# CH32V305FBP6-R0.net
KiCad netlist of a schematic drawn in Altium Designer
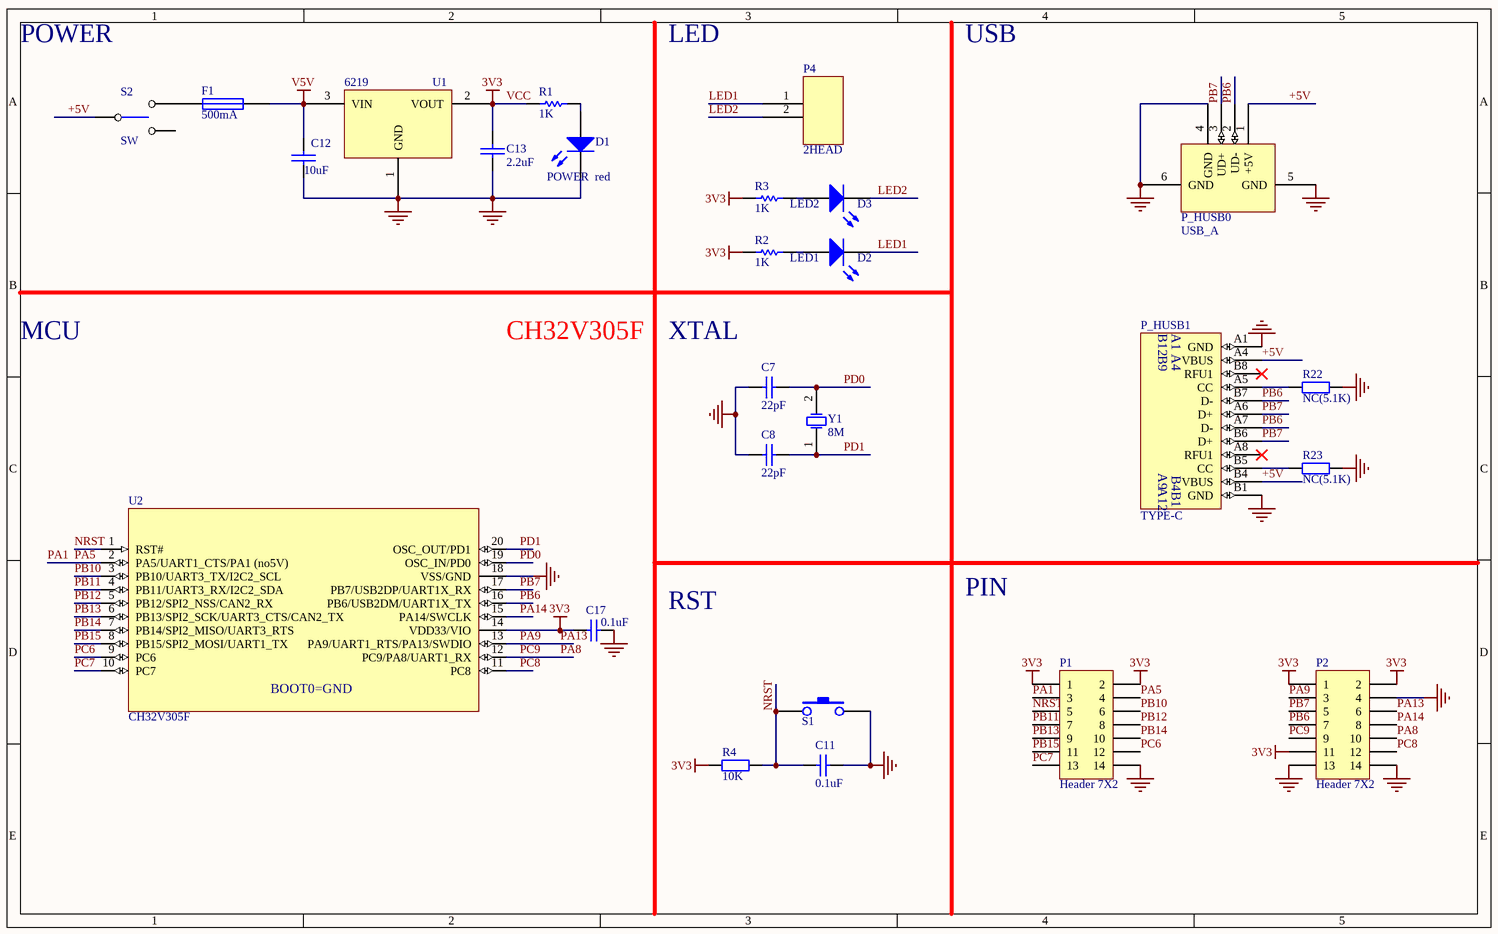
[diagram p0: CH32V305FBP6-R0.SchDoc]

(export (version "E")
  (design (tool "Eeschema 10.0.6"))
  (components
    (comp (ref "C7")
      (value "22pF")
      (footprint "0603_C")
      (description "Capacitor")
      (fields (field (name "PUBLISHER") "Altium Limited"))
      (libsource (lib "*") (part "Cap"))
    )
    (comp (ref "C8")
      (value "22pF")
      (footprint "0603_C")
      (description "Capacitor")
      (fields (field (name "PUBLISHER") "Altium Limited"))
      (libsource (lib "*") (part "Cap"))
    )
    (comp (ref "C11")
      (value "0.1uF")
      (footprint "0603_C")
      (description "Capacitor")
      (fields (field (name "PUBLISHER") "Altium Limited"))
      (libsource (lib "*") (part "Cap"))
    )
    (comp (ref "C12")
      (value "10uF")
      (footprint "3216_C")
      (description "Capacitor")
      (libsource (lib "*") (part "CAP"))
    )
    (comp (ref "C13")
      (value "2.2uF")
      (footprint "0603_C")
      (description "Capacitor")
      (libsource (lib "*") (part "CAP"))
    )
    (comp (ref "C17")
      (value "0.1uF")
      (footprint "0603_C")
      (description "Capacitor")
      (fields (field (name "PUBLISHER") "Altium Limited"))
      (libsource (lib "*") (part "Cap"))
    )
    (comp (ref "D1")
      (value "POWER  red")
      (footprint "0603+")
      (description "Typical INFRARED GaAs LED")
      (fields (field (name "PUBLISHER") "Altium Limited"))
      (libsource (lib "*") (part "LED0"))
    )
    (comp (ref "D2")
      (value "LED1")
      (footprint "0603+")
      (description "Typical INFRARED GaAs LED")
      (fields (field (name "PUBLISHER") "Altium Limited"))
      (libsource (lib "*") (part "LED0"))
    )
    (comp (ref "D3")
      (value "LED2")
      (footprint "0603+")
      (description "Typical INFRARED GaAs LED")
      (fields (field (name "PUBLISHER") "Altium Limited"))
      (libsource (lib "*") (part "LED0"))
    )
    (comp (ref "F1")
      (value "500mA")
      (footprint "0603")
      (description "Fuse")
      (libsource (lib "*") (part "FUSE1"))
    )
    (comp (ref "P1")
      (value "Header 7X2")
      (footprint "IDC14-2.54mm")
      (description "Header, 7-Pin, Dual row")
      (fields (field (name "PUBLISHER") "Altium Limited"))
      (libsource (lib "Miscellaneous Connectors") (part "Header 7X2"))
    )
    (comp (ref "P2")
      (value "Header 7X2")
      (footprint "IDC14-2.54mm")
      (description "Header, 7-Pin, Dual row")
      (fields (field (name "PUBLISHER") "Altium Limited"))
      (libsource (lib "Miscellaneous Connectors") (part "Header 7X2"))
    )
    (comp (ref "P4") (value "2HEAD") (footprint "SIP2-2.54mm") (libsource (lib "*") (part "2HEAD")))
    (comp (ref "P_HUSB0")
      (value "USB_A")
      (footprint "USBAF")
      (description "USB Port")
      (libsource (lib "*") (part "USB"))
    )
    (comp (ref "P_HUSB1")
      (value "TYPE-C")
      (footprint "TYPE-C-Receptacle-2.0")
      (libsource (lib "*") (part "TYPE-C1"))
    )
    (comp (ref "R1")
      (value "1K")
      (footprint "0603")
      (description "Semiconductor Resistor")
      (fields (field (name "PUBLISHER") "Altium Limited"))
      (libsource (lib "*") (part "Res Semi"))
    )
    (comp (ref "R2")
      (value "1K")
      (footprint "0603")
      (description "Semiconductor Resistor")
      (fields (field (name "PUBLISHER") "Altium Limited"))
      (libsource (lib "*") (part "Res Semi"))
    )
    (comp (ref "R3")
      (value "1K")
      (footprint "0603")
      (description "Semiconductor Resistor")
      (fields (field (name "PUBLISHER") "Altium Limited"))
      (libsource (lib "*") (part "Res Semi"))
    )
    (comp (ref "R4")
      (value "10K")
      (footprint "0603")
      (description "Resistor")
      (fields (field (name "PUBLISHER") "Altium Limited"))
      (libsource (lib "*") (part "Res2"))
    )
    (comp (ref "R22")
      (value "NC(5.1K)")
      (footprint "0603")
      (description "Resistor")
      (libsource (lib "Miscellaneous Devices") (part "Res2"))
    )
    (comp (ref "R23")
      (value "NC(5.1K)")
      (footprint "0603")
      (description "Resistor")
      (libsource (lib "Miscellaneous Devices") (part "Res2"))
    )
    (comp (ref "S1") (value "KEY") (footprint "SMD_6.1x3.65x2.5mm-KEY") (libsource (lib "*") (part "KEY")))
    (comp (ref "S2") (value "SW") (footprint "KEY2") (libsource (lib "*") (part "SW")))
    (comp (ref "U1") (value "6219") (footprint "SOT-23") (libsource (lib "*") (part "LM1117_3.3V")))
    (comp (ref "U2")
      (value "CH32V305F")
      (footprint "TSSOP20")
      (description "RISC-V FPU HD-MCU, 144MHz, USB_480M, CAN, UART*2, SPI")
      (libsource (lib "CHXXX") (part "CH32V305F"))
    )
    (comp (ref "Y1")
      (value "8M")
      (footprint "XT_AT49")
      (description "Crystal Oscillator")
      (fields (field (name "PUBLISHER") "Altium Limited"))
      (libsource (lib "*") (part "XTAL"))
    )
  )
  (nets
    (net (code "1") (name "/+5V") (class "Default")
      (node (ref "P_HUSB0") (pin "1") (pinfunction "+5V_1") (pintype "power_in"))
      (node (ref "P_HUSB1") (pin "A4") (pinfunction "VBUS_A4") (pintype "bidirectional"))
      (node (ref "P_HUSB1") (pin "B4") (pinfunction "VBUS_B4") (pintype "bidirectional"))
      (node (ref "S2") (pin "1") (pinfunction "1_1") (pintype "passive"))
    )
    (net (code "3") (name "/LED1") (class "Default")
      (node (ref "D2") (pin "2") (pinfunction "K_2") (pintype "passive"))
      (node (ref "P4") (pin "1") (pintype "passive"))
    )
    (net (code "4") (name "/LED2") (class "Default")
      (node (ref "D3") (pin "2") (pinfunction "K_2") (pintype "passive"))
      (node (ref "P4") (pin "2") (pintype "passive"))
    )
    (net (code "5") (name "/NRST") (class "Default")
      (node (ref "C11") (pin "2") (pinfunction "2_2") (pintype "passive"))
      (node (ref "P1") (pin "5") (pinfunction "5_5") (pintype "passive"))
      (node (ref "R4") (pin "1") (pinfunction "1_1") (pintype "passive"))
      (node (ref "S1") (pin "1") (pinfunction "1_1") (pintype "passive"))
      (node (ref "U2") (pin "1") (pinfunction "RST#_1") (pintype "input"))
    )
    (net (code "6") (name "/PA1") (class "Default")
      (node (ref "P1") (pin "3") (pinfunction "3_3") (pintype "passive"))
      (node (ref "P1") (pin "4") (pinfunction "4_4") (pintype "passive"))
      (node (ref "U2") (pin "2") (pinfunction "PA5/UART1_CTS/PA1_(no5V)_2") (pintype "bidirectional"))
    )
    (net (code "7") (name "/PA8") (class "Default")
      (node (ref "P2") (pin "10") (pinfunction "10_10") (pintype "passive"))
      (node (ref "P2") (pin "9") (pinfunction "9_9") (pintype "passive"))
      (node (ref "U2") (pin "12") (pinfunction "PC9/PA8/UART1_RX_12") (pintype "bidirectional"))
    )
    (net (code "8") (name "/PA13") (class "Default")
      (node (ref "P2") (pin "3") (pinfunction "3_3") (pintype "passive"))
      (node (ref "P2") (pin "6") (pinfunction "6_6") (pintype "passive"))
      (node (ref "U2") (pin "13") (pinfunction "PA9/UART1_RTS/PA13/SWDIO_13") (pintype "bidirectional"))
    )
    (net (code "9") (name "/PA14") (class "Default")
      (node (ref "P2") (pin "8") (pinfunction "8_8") (pintype "passive"))
      (node (ref "U2") (pin "15") (pinfunction "PA14/SWCLK_15") (pintype "bidirectional"))
    )
    (net (code "10") (name "/PB6") (class "Default")
      (node (ref "P2") (pin "7") (pinfunction "7_7") (pintype "passive"))
      (node (ref "P_HUSB0") (pin "2") (pinfunction "UD-_2") (pintype "bidirectional"))
      (node (ref "P_HUSB1") (pin "A7") (pinfunction "D-_A7") (pintype "bidirectional"))
      (node (ref "P_HUSB1") (pin "B7") (pinfunction "D-_B7") (pintype "bidirectional"))
      (node (ref "U2") (pin "16") (pinfunction "PB6/USB2DM/UART1X_TX_16") (pintype "bidirectional"))
    )
    (net (code "11") (name "/PB7") (class "Default")
      (node (ref "P2") (pin "5") (pinfunction "5_5") (pintype "passive"))
      (node (ref "P_HUSB0") (pin "3") (pinfunction "UD+_3") (pintype "bidirectional"))
      (node (ref "P_HUSB1") (pin "A6") (pinfunction "D+_A6") (pintype "bidirectional"))
      (node (ref "P_HUSB1") (pin "B6") (pinfunction "D+_B6") (pintype "bidirectional"))
      (node (ref "U2") (pin "17") (pinfunction "PB7/USB2DP/UART1X_RX_17") (pintype "bidirectional"))
    )
    (net (code "12") (name "/PB10") (class "Default")
      (node (ref "P1") (pin "6") (pinfunction "6_6") (pintype "passive"))
      (node (ref "U2") (pin "3") (pinfunction "PB10/UART3_TX/I2C2_SCL_3") (pintype "bidirectional"))
    )
    (net (code "13") (name "/PB11") (class "Default")
      (node (ref "P1") (pin "7") (pinfunction "7_7") (pintype "passive"))
      (node (ref "U2") (pin "4") (pinfunction "PB11/UART3_RX/I2C2_SDA_4") (pintype "bidirectional"))
    )
    (net (code "14") (name "/PB12") (class "Default")
      (node (ref "P1") (pin "8") (pinfunction "8_8") (pintype "passive"))
      (node (ref "U2") (pin "5") (pinfunction "PB12/SPI2_NSS/CAN2_RX_5") (pintype "bidirectional"))
    )
    (net (code "15") (name "/PB13") (class "Default")
      (node (ref "P1") (pin "9") (pinfunction "9_9") (pintype "passive"))
      (node (ref "U2") (pin "6") (pinfunction "PB13/SPI2_SCK/UART3_CTS/CAN2_TX_6") (pintype "bidirectional"))
    )
    (net (code "16") (name "/PB14") (class "Default")
      (node (ref "P1") (pin "10") (pinfunction "10_10") (pintype "passive"))
      (node (ref "U2") (pin "7") (pinfunction "PB14/SPI2_MISO/UART3_RTS_7") (pintype "bidirectional"))
    )
    (net (code "17") (name "/PB15") (class "Default")
      (node (ref "P1") (pin "11") (pinfunction "11_11") (pintype "passive"))
      (node (ref "U2") (pin "8") (pinfunction "PB15/SPI2_MOSI/UART1_TX_8") (pintype "bidirectional"))
    )
    (net (code "18") (name "/PC6") (class "Default")
      (node (ref "P1") (pin "12") (pinfunction "12_12") (pintype "passive"))
      (node (ref "U2") (pin "9") (pinfunction "PC6_9") (pintype "bidirectional"))
    )
    (net (code "19") (name "/PC7") (class "Default")
      (node (ref "P1") (pin "13") (pinfunction "13_13") (pintype "passive"))
      (node (ref "U2") (pin "10") (pinfunction "PC7_10") (pintype "bidirectional"))
    )
    (net (code "20") (name "/PC8") (class "Default")
      (node (ref "P2") (pin "12") (pinfunction "12_12") (pintype "passive"))
      (node (ref "U2") (pin "11") (pinfunction "PC8_11") (pintype "bidirectional"))
    )
    (net (code "21") (name "/PD0") (class "Default")
      (node (ref "C7") (pin "2") (pinfunction "2_2") (pintype "passive"))
      (node (ref "U2") (pin "19") (pinfunction "OSC_IN/PD0_19") (pintype "bidirectional"))
      (node (ref "Y1") (pin "2") (pinfunction "OSC2_2") (pintype "passive"))
    )
    (net (code "22") (name "/PD1") (class "Default")
      (node (ref "C8") (pin "2") (pinfunction "2_2") (pintype "passive"))
      (node (ref "U2") (pin "20") (pinfunction "OSC_OUT/PD1_20") (pintype "bidirectional"))
      (node (ref "Y1") (pin "1") (pinfunction "OSC1_1") (pintype "passive"))
    )
    (net (code "23") (name "3V3") (class "Default")
      (node (ref "C13") (pin "1") (pinfunction "1_1") (pintype "passive"))
      (node (ref "C17") (pin "2") (pinfunction "2_2") (pintype "passive"))
      (node (ref "P1") (pin "1") (pinfunction "1_1") (pintype "passive"))
      (node (ref "P1") (pin "2") (pinfunction "2_2") (pintype "passive"))
      (node (ref "P2") (pin "1") (pinfunction "1_1") (pintype "passive"))
      (node (ref "P2") (pin "11") (pinfunction "11_11") (pintype "passive"))
      (node (ref "P2") (pin "2") (pinfunction "2_2") (pintype "passive"))
      (node (ref "R1") (pin "2") (pinfunction "2_2") (pintype "passive"))
      (node (ref "R2") (pin "1") (pinfunction "1_1") (pintype "passive"))
      (node (ref "R3") (pin "1") (pinfunction "1_1") (pintype "passive"))
      (node (ref "R4") (pin "2") (pinfunction "2_2") (pintype "passive"))
      (node (ref "U1") (pin "2") (pinfunction "VOUT_2") (pintype "passive"))
      (node (ref "U2") (pin "14") (pinfunction "VDD33/VIO_14") (pintype "power_in"))
    )
    (net (code "24") (name "GND") (class "Default")
      (node (ref "C11") (pin "1") (pinfunction "1_1") (pintype "passive"))
      (node (ref "C12") (pin "2") (pinfunction "2_2") (pintype "passive"))
      (node (ref "C13") (pin "2") (pinfunction "2_2") (pintype "passive"))
      (node (ref "C17") (pin "1") (pinfunction "1_1") (pintype "passive"))
      (node (ref "C7") (pin "1") (pinfunction "1_1") (pintype "passive"))
      (node (ref "C8") (pin "1") (pinfunction "1_1") (pintype "passive"))
      (node (ref "D1") (pin "2") (pinfunction "K_2") (pintype "passive"))
      (node (ref "P1") (pin "14") (pinfunction "14_14") (pintype "passive"))
      (node (ref "P2") (pin "13") (pinfunction "13_13") (pintype "passive"))
      (node (ref "P2") (pin "14") (pinfunction "14_14") (pintype "passive"))
      (node (ref "P2") (pin "4") (pinfunction "4_4") (pintype "passive"))
      (node (ref "P_HUSB0") (pin "4") (pinfunction "GND_4") (pintype "power_in"))
      (node (ref "P_HUSB0") (pin "5") (pinfunction "GND_5") (pintype "power_in"))
      (node (ref "P_HUSB0") (pin "6") (pinfunction "GND_6") (pintype "power_in"))
      (node (ref "P_HUSB1") (pin "A1") (pinfunction "GND_A1") (pintype "bidirectional"))
      (node (ref "P_HUSB1") (pin "B1") (pinfunction "GND_B1") (pintype "bidirectional"))
      (node (ref "R22") (pin "2") (pinfunction "2_2") (pintype "passive"))
      (node (ref "R23") (pin "2") (pinfunction "2_2") (pintype "passive"))
      (node (ref "S1") (pin "3") (pinfunction "3_3") (pintype "passive"))
      (node (ref "U1") (pin "1") (pinfunction "GND_1") (pintype "passive"))
      (node (ref "U2") (pin "18") (pinfunction "VSS/GND_18") (pintype "power_in"))
    )
    (net (code "25") (name "Net-(D1-A)") (class "Default")
      (node (ref "D1") (pin "1") (pinfunction "A_1") (pintype "passive"))
      (node (ref "R1") (pin "1") (pinfunction "1_1") (pintype "passive"))
    )
    (net (code "26") (name "Net-(D2-A)") (class "Default")
      (node (ref "D2") (pin "1") (pinfunction "A_1") (pintype "passive"))
      (node (ref "R2") (pin "2") (pinfunction "2_2") (pintype "passive"))
    )
    (net (code "27") (name "Net-(D3-A)") (class "Default")
      (node (ref "D3") (pin "1") (pinfunction "A_1") (pintype "passive"))
      (node (ref "R3") (pin "2") (pinfunction "2_2") (pintype "passive"))
    )
    (net (code "28") (name "Net-(F1-Pad1)") (class "Default")
      (node (ref "F1") (pin "1") (pinfunction "1_1") (pintype "passive"))
      (node (ref "S2") (pin "3") (pinfunction "3_3") (pintype "passive"))
    )
    (net (code "29") (name "Net-(P_HUSB1-CC-PadA5)") (class "Default")
      (node (ref "P_HUSB1") (pin "A5") (pinfunction "CC_A5") (pintype "bidirectional"))
      (node (ref "R22") (pin "1") (pinfunction "1_1") (pintype "passive"))
    )
    (net (code "30") (name "Net-(P_HUSB1-CC-PadB5)") (class "Default")
      (node (ref "P_HUSB1") (pin "B5") (pinfunction "CC_B5") (pintype "bidirectional"))
      (node (ref "R23") (pin "1") (pinfunction "1_1") (pintype "passive"))
    )
    (net (code "31") (name "V5V") (class "Default")
      (node (ref "C12") (pin "1") (pinfunction "1_1") (pintype "passive"))
      (node (ref "F1") (pin "2") (pinfunction "2_2") (pintype "passive"))
      (node (ref "U1") (pin "3") (pinfunction "VIN_3") (pintype "passive"))
    )
    (net (code "32") (name "unconnected-(P_HUSB1-RFU1-PadA8)") (class "Default")
      (node (ref "P_HUSB1") (pin "A8") (pinfunction "RFU1_A8") (pintype "bidirectional+no_connect"))
    )
    (net (code "33") (name "unconnected-(P_HUSB1-RFU1-PadB8)") (class "Default")
      (node (ref "P_HUSB1") (pin "B8") (pinfunction "RFU1_B8") (pintype "bidirectional+no_connect"))
    )
    (net (code "34") (name "unconnected-(S2-Pad2)") (class "Default")
      (node (ref "S2") (pin "2") (pinfunction "2_2") (pintype "passive"))
    )
  )
)
